# MCU.net
KiCad netlist of a schematic drawn in Altium Designer
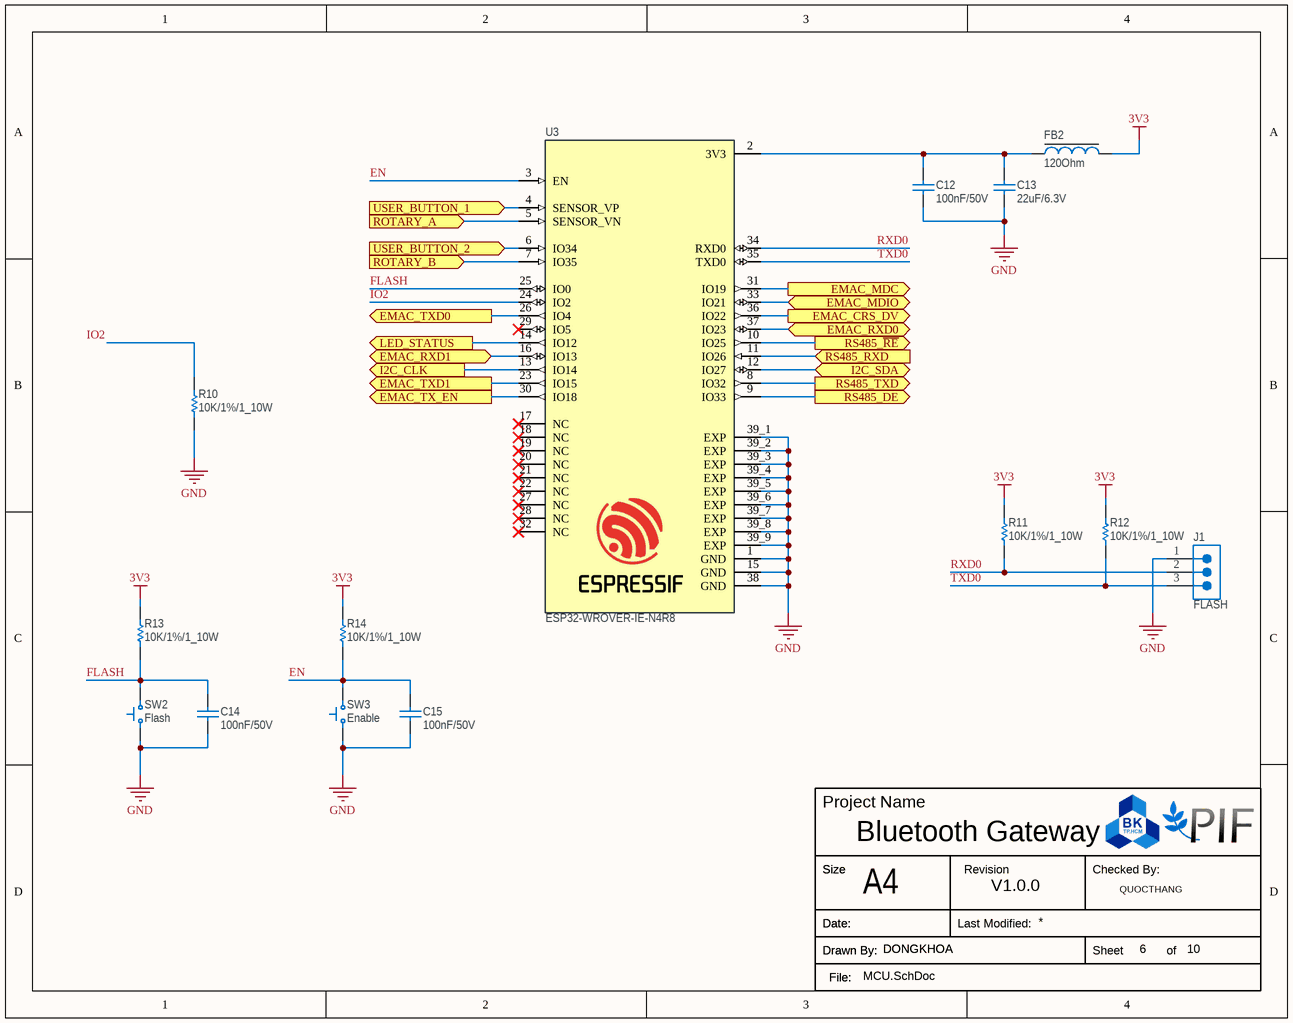
[diagram p0: MCU.SchDoc]

(export (version "E")
  (design (tool "Eeschema 10.0.6"))
  (components
    (comp (ref "C12")
      (value "100nF/50V")
      (footprint "CAP_0805")
      (description "CAP, size 0805, 100nF, 50V")
      (fields (field (name "SUPPLY PART NUMBER") "Tụ Gốm 0805 100nF (0.1uF) 50V"))
      (libsource (lib "BluetoothTracking") (part "Ceramic_Cap_100nF_50V_0805"))
    )
    (comp (ref "C13")
      (value "22uF/6.3V")
      (footprint "CAP_0805")
      (description "CAP, size 0805, 22uF, 6.3V")
      (fields (field (name "SUPPLY PART NUMBER") "Tụ Gốm 0805 22uF 6.3V"))
      (libsource (lib "BluetoothTracking") (part "Ceramic_Cap_22uF_6.3V_0805"))
    )
    (comp (ref "C14")
      (value "100nF/50V")
      (footprint "CAP_0603")
      (description "CAP, size 0603, 100nF, 50V")
      (fields (field (name "SUPPLY PART NUMBER") "Tụ Gốm 0603 100nF (0.1uF) 50V"))
      (libsource (lib "BluetoothTracking") (part "Ceramic_Cap_100nF_50V_0603"))
    )
    (comp (ref "C15")
      (value "100nF/50V")
      (footprint "CAP_0603")
      (description "CAP, size 0603, 100nF, 50V")
      (fields (field (name "SUPPLY PART NUMBER") "Tụ Gốm 0603 100nF (0.1uF) 50V"))
      (libsource (lib "BluetoothTracking") (part "Ceramic_Cap_100nF_50V_0603"))
    )
    (comp (ref "FB2")
      (value "120Ohm")
      (footprint "Ferrite_Bead_0805")
      (description "Ferrite Bead, size 0805, 120Ohm, 2A")
      (fields (field (name "SUPPLY PART NUMBER") "CBW201209U121T Ferrite Beads 2A 120 Ohm 0805"))
      (libsource (lib "BluetoothTracking") (part "Ferrite_Bead_120Ohm_2A_0805"))
    )
    (comp (ref "J1")
      (value "FLASH")
      (footprint "Header_2.54mm_3P")
      (description "Hàng Rào Đực Đơn 2.54mm 40 Chân 1 Hàng Cao 11.2mm Xuyên Lỗ")
      (libsource (lib "BluetoothTracking") (part "Header_2.54mm_3P"))
    )
    (comp (ref "R10")
      (value "10K/1%/1_10W")
      (footprint "Resistor_0603")
      (description "Resistor 0603 10KOhm 1% 1_10W")
      (fields (field (name "SUPPLY PART NUMBER") "Điện Trở 10 KOhm 0603 1%"))
      (libsource (lib "BluetoothTracking") (part "Res_10K_0603_1%"))
    )
    (comp (ref "R11")
      (value "10K/1%/1_10W")
      (footprint "Resistor_0603")
      (description "Resistor 0603 10KOhm 1% 1_10W")
      (fields (field (name "SUPPLY PART NUMBER") "Điện Trở 10 KOhm 0603 1%"))
      (libsource (lib "BluetoothTracking") (part "Res_10K_0603_1%"))
    )
    (comp (ref "R12")
      (value "10K/1%/1_10W")
      (footprint "Resistor_0603")
      (description "Resistor 0603 10KOhm 1% 1_10W")
      (fields (field (name "SUPPLY PART NUMBER") "Điện Trở 10 KOhm 0603 1%"))
      (libsource (lib "BluetoothTracking") (part "Res_10K_0603_1%"))
    )
    (comp (ref "R13")
      (value "10K/1%/1_10W")
      (footprint "Resistor_0603")
      (description "Resistor 0603 10KOhm 1% 1_10W")
      (fields (field (name "SUPPLY PART NUMBER") "Điện Trở 10 KOhm 0603 1%"))
      (libsource (lib "BluetoothTracking") (part "Res_10K_0603_1%"))
    )
    (comp (ref "R14")
      (value "10K/1%/1_10W")
      (footprint "Resistor_0603")
      (description "Resistor 0603 10KOhm 1% 1_10W")
      (fields (field (name "SUPPLY PART NUMBER") "Điện Trở 10 KOhm 0603 1%"))
      (libsource (lib "BluetoothTracking") (part "Res_10K_0603_1%"))
    )
    (comp (ref "SW2")
      (value "Flash")
      (footprint "Button_3x4mm_SMD_2P")
      (fields (field (name "SUPPLY PART NUMBER") "Nút Nhấn 3x4mm Cao 2.5mm 2 Chân SMD"))
      (libsource (lib "BluetoothTracking") (part "Button_SMD_3x4mm_2P"))
    )
    (comp (ref "SW3")
      (value "Enable")
      (footprint "Button_3x4mm_SMD_2P")
      (fields (field (name "SUPPLY PART NUMBER") "Nút Nhấn 3x4mm Cao 2.5mm 2 Chân SMD"))
      (libsource (lib "BluetoothTracking") (part "Button_SMD_3x4mm_2P"))
    )
    (comp (ref "U3")
      (value "ESP32-WROVER-IE-N4R8")
      (footprint "XCVR_ESP32-WROVER-IE-N4R8")
      (fields
        (field (name "SUPPLY PART NUMBER") "ESP32-WROVER-IE-N4R8 Module WiFi Bluetooth 4MB Flash, 8MB PSRAM, 2.4GHz")
      )
      (libsource (lib "BluetoothTracking") (part "ESP32-WROVER-IE-N4R8"))
    )
  )
  (nets
    (net (code "1") (name "/EMAC_CRS_DV") (class "Default")
      (node (ref "U3") (pin "36") (pinfunction "IO22_36") (pintype "output"))
    )
    (net (code "2") (name "/EMAC_MDC") (class "Default")
      (node (ref "U3") (pin "31") (pinfunction "IO19_31") (pintype "output"))
    )
    (net (code "3") (name "/EMAC_MDIO") (class "Default")
      (node (ref "U3") (pin "33") (pinfunction "IO21_33") (pintype "bidirectional"))
    )
    (net (code "4") (name "/EMAC_RXD0") (class "Default")
      (node (ref "U3") (pin "37") (pinfunction "IO23_37") (pintype "bidirectional"))
    )
    (net (code "5") (name "/EMAC_RXD1") (class "Default")
      (node (ref "U3") (pin "16") (pinfunction "IO13_16") (pintype "bidirectional"))
    )
    (net (code "6") (name "/EMAC_TXD0") (class "Default")
      (node (ref "U3") (pin "26") (pinfunction "IO4_26") (pintype "output"))
    )
    (net (code "7") (name "/EMAC_TXD1") (class "Default")
      (node (ref "U3") (pin "23") (pinfunction "IO15_23") (pintype "output"))
    )
    (net (code "8") (name "/EMAC_TX_EN") (class "Default")
      (node (ref "U3") (pin "30") (pinfunction "IO18_30") (pintype "output"))
    )
    (net (code "9") (name "/EN") (class "Default")
      (node (ref "C15") (pin "2") (pinfunction "2_2") (pintype "passive"))
      (node (ref "R14") (pin "1") (pinfunction "1_1") (pintype "passive"))
      (node (ref "SW3") (pin "2") (pinfunction "2_2") (pintype "passive"))
      (node (ref "U3") (pin "3") (pinfunction "EN_3") (pintype "input"))
    )
    (net (code "10") (name "/FLASH") (class "Default")
      (node (ref "C14") (pin "2") (pinfunction "2_2") (pintype "passive"))
      (node (ref "R13") (pin "1") (pinfunction "1_1") (pintype "passive"))
      (node (ref "SW2") (pin "2") (pinfunction "2_2") (pintype "passive"))
      (node (ref "U3") (pin "25") (pinfunction "IO0_25") (pintype "bidirectional"))
    )
    (net (code "11") (name "/I2C_CLK") (class "Default")
      (node (ref "U3") (pin "13") (pinfunction "IO14_13") (pintype "output"))
    )
    (net (code "12") (name "/I2C_SDA") (class "Default")
      (node (ref "U3") (pin "12") (pinfunction "IO27_12") (pintype "bidirectional"))
    )
    (net (code "13") (name "/IO2") (class "Default")
      (node (ref "R10") (pin "2") (pinfunction "2_2") (pintype "passive"))
      (node (ref "U3") (pin "24") (pinfunction "IO2_24") (pintype "bidirectional"))
    )
    (net (code "14") (name "/LED_STATUS") (class "Default")
      (node (ref "U3") (pin "14") (pinfunction "IO12_14") (pintype "output"))
    )
    (net (code "15") (name "/ROTARY_A") (class "Default")
      (node (ref "U3") (pin "5") (pinfunction "SENSOR_VN_5") (pintype "input"))
    )
    (net (code "16") (name "/ROTARY_B") (class "Default")
      (node (ref "U3") (pin "7") (pinfunction "IO35_7") (pintype "input"))
    )
    (net (code "17") (name "/RS485_DE") (class "Default")
      (node (ref "U3") (pin "9") (pinfunction "IO33_9") (pintype "output"))
    )
    (net (code "18") (name "/RS485_RXD") (class "Default")
      (node (ref "U3") (pin "11") (pinfunction "IO26_11") (pintype "input"))
    )
    (net (code "19") (name "/RS485_TXD") (class "Default")
      (node (ref "U3") (pin "8") (pinfunction "IO32_8") (pintype "output"))
    )
    (net (code "20") (name "/RS485_~{RE}") (class "Default")
      (node (ref "U3") (pin "10") (pinfunction "IO25_10") (pintype "output"))
    )
    (net (code "21") (name "/RXD0") (class "Default")
      (node (ref "J1") (pin "2") (pinfunction "2_2") (pintype "passive"))
      (node (ref "R11") (pin "1") (pinfunction "1_1") (pintype "passive"))
      (node (ref "U3") (pin "34") (pinfunction "RXD0_34") (pintype "bidirectional"))
    )
    (net (code "22") (name "/TXD0") (class "Default")
      (node (ref "J1") (pin "3") (pinfunction "3_3") (pintype "passive"))
      (node (ref "R12") (pin "1") (pinfunction "1_1") (pintype "passive"))
      (node (ref "U3") (pin "35") (pinfunction "TXD0_35") (pintype "bidirectional"))
    )
    (net (code "23") (name "/USER_BUTTON_1") (class "Default")
      (node (ref "U3") (pin "4") (pinfunction "SENSOR_VP_4") (pintype "input"))
    )
    (net (code "24") (name "/USER_BUTTON_2") (class "Default")
      (node (ref "U3") (pin "6") (pinfunction "IO34_6") (pintype "input"))
    )
    (net (code "25") (name "3V3") (class "Default")
      (node (ref "FB2") (pin "2") (pinfunction "2_2") (pintype "passive"))
      (node (ref "R11") (pin "2") (pinfunction "2_2") (pintype "passive"))
      (node (ref "R12") (pin "2") (pinfunction "2_2") (pintype "passive"))
      (node (ref "R13") (pin "2") (pinfunction "2_2") (pintype "passive"))
      (node (ref "R14") (pin "2") (pinfunction "2_2") (pintype "passive"))
    )
    (net (code "26") (name "GND") (class "Default")
      (node (ref "C12") (pin "1") (pinfunction "1_1") (pintype "passive"))
      (node (ref "C13") (pin "1") (pinfunction "1_1") (pintype "passive"))
      (node (ref "C14") (pin "1") (pinfunction "1_1") (pintype "passive"))
      (node (ref "C15") (pin "1") (pinfunction "1_1") (pintype "passive"))
      (node (ref "J1") (pin "1") (pinfunction "1_1") (pintype "passive"))
      (node (ref "R10") (pin "1") (pinfunction "1_1") (pintype "passive"))
      (node (ref "SW2") (pin "1") (pinfunction "1_1") (pintype "passive"))
      (node (ref "SW3") (pin "1") (pinfunction "1_1") (pintype "passive"))
      (node (ref "U3") (pin "1") (pinfunction "GND_1") (pintype "power_in"))
      (node (ref "U3") (pin "15") (pinfunction "GND_15") (pintype "power_in"))
      (node (ref "U3") (pin "38") (pinfunction "GND_38") (pintype "power_in"))
      (node (ref "U3") (pin "39_1") (pinfunction "EXP_39_1") (pintype "power_in"))
      (node (ref "U3") (pin "39_2") (pinfunction "EXP_39_2") (pintype "power_in"))
      (node (ref "U3") (pin "39_3") (pinfunction "EXP_39_3") (pintype "power_in"))
      (node (ref "U3") (pin "39_4") (pinfunction "EXP_39_4") (pintype "power_in"))
      (node (ref "U3") (pin "39_5") (pinfunction "EXP_39_5") (pintype "power_in"))
      (node (ref "U3") (pin "39_6") (pinfunction "EXP_39_6") (pintype "power_in"))
      (node (ref "U3") (pin "39_7") (pinfunction "EXP_39_7") (pintype "power_in"))
      (node (ref "U3") (pin "39_8") (pinfunction "EXP_39_8") (pintype "power_in"))
      (node (ref "U3") (pin "39_9") (pinfunction "EXP_39_9") (pintype "power_in"))
    )
    (net (code "27") (name "Net-(U3-3V3)") (class "Default")
      (node (ref "C12") (pin "2") (pinfunction "2_2") (pintype "passive"))
      (node (ref "C13") (pin "2") (pinfunction "2_2") (pintype "passive"))
      (node (ref "FB2") (pin "1") (pinfunction "1_1") (pintype "passive"))
      (node (ref "U3") (pin "2") (pinfunction "3V3_2") (pintype "power_in"))
    )
    (net (code "28") (name "unconnected-(U3-IO5-Pad29)") (class "Default")
      (node (ref "U3") (pin "29") (pinfunction "IO5_29") (pintype "bidirectional+no_connect"))
    )
    (net (code "29") (name "unconnected-(U3-NC-Pad17)") (class "Default")
      (node (ref "U3") (pin "17") (pinfunction "NC_17") (pintype "passive+no_connect"))
    )
    (net (code "30") (name "unconnected-(U3-NC-Pad18)") (class "Default")
      (node (ref "U3") (pin "18") (pinfunction "NC_18") (pintype "passive+no_connect"))
    )
    (net (code "31") (name "unconnected-(U3-NC-Pad19)") (class "Default")
      (node (ref "U3") (pin "19") (pinfunction "NC_19") (pintype "passive+no_connect"))
    )
    (net (code "32") (name "unconnected-(U3-NC-Pad20)") (class "Default")
      (node (ref "U3") (pin "20") (pinfunction "NC_20") (pintype "passive+no_connect"))
    )
    (net (code "33") (name "unconnected-(U3-NC-Pad21)") (class "Default")
      (node (ref "U3") (pin "21") (pinfunction "NC_21") (pintype "passive+no_connect"))
    )
    (net (code "34") (name "unconnected-(U3-NC-Pad22)") (class "Default")
      (node (ref "U3") (pin "22") (pinfunction "NC_22") (pintype "passive+no_connect"))
    )
    (net (code "35") (name "unconnected-(U3-NC-Pad27)") (class "Default")
      (node (ref "U3") (pin "27") (pinfunction "NC_27") (pintype "passive+no_connect"))
    )
    (net (code "36") (name "unconnected-(U3-NC-Pad28)") (class "Default")
      (node (ref "U3") (pin "28") (pinfunction "NC_28") (pintype "passive+no_connect"))
    )
    (net (code "37") (name "unconnected-(U3-NC-Pad32)") (class "Default")
      (node (ref "U3") (pin "32") (pinfunction "NC_32") (pintype "passive+no_connect"))
    )
  )
)
